# crypto_programmer.net
KiCad netlist of a schematic drawn in EAGLE
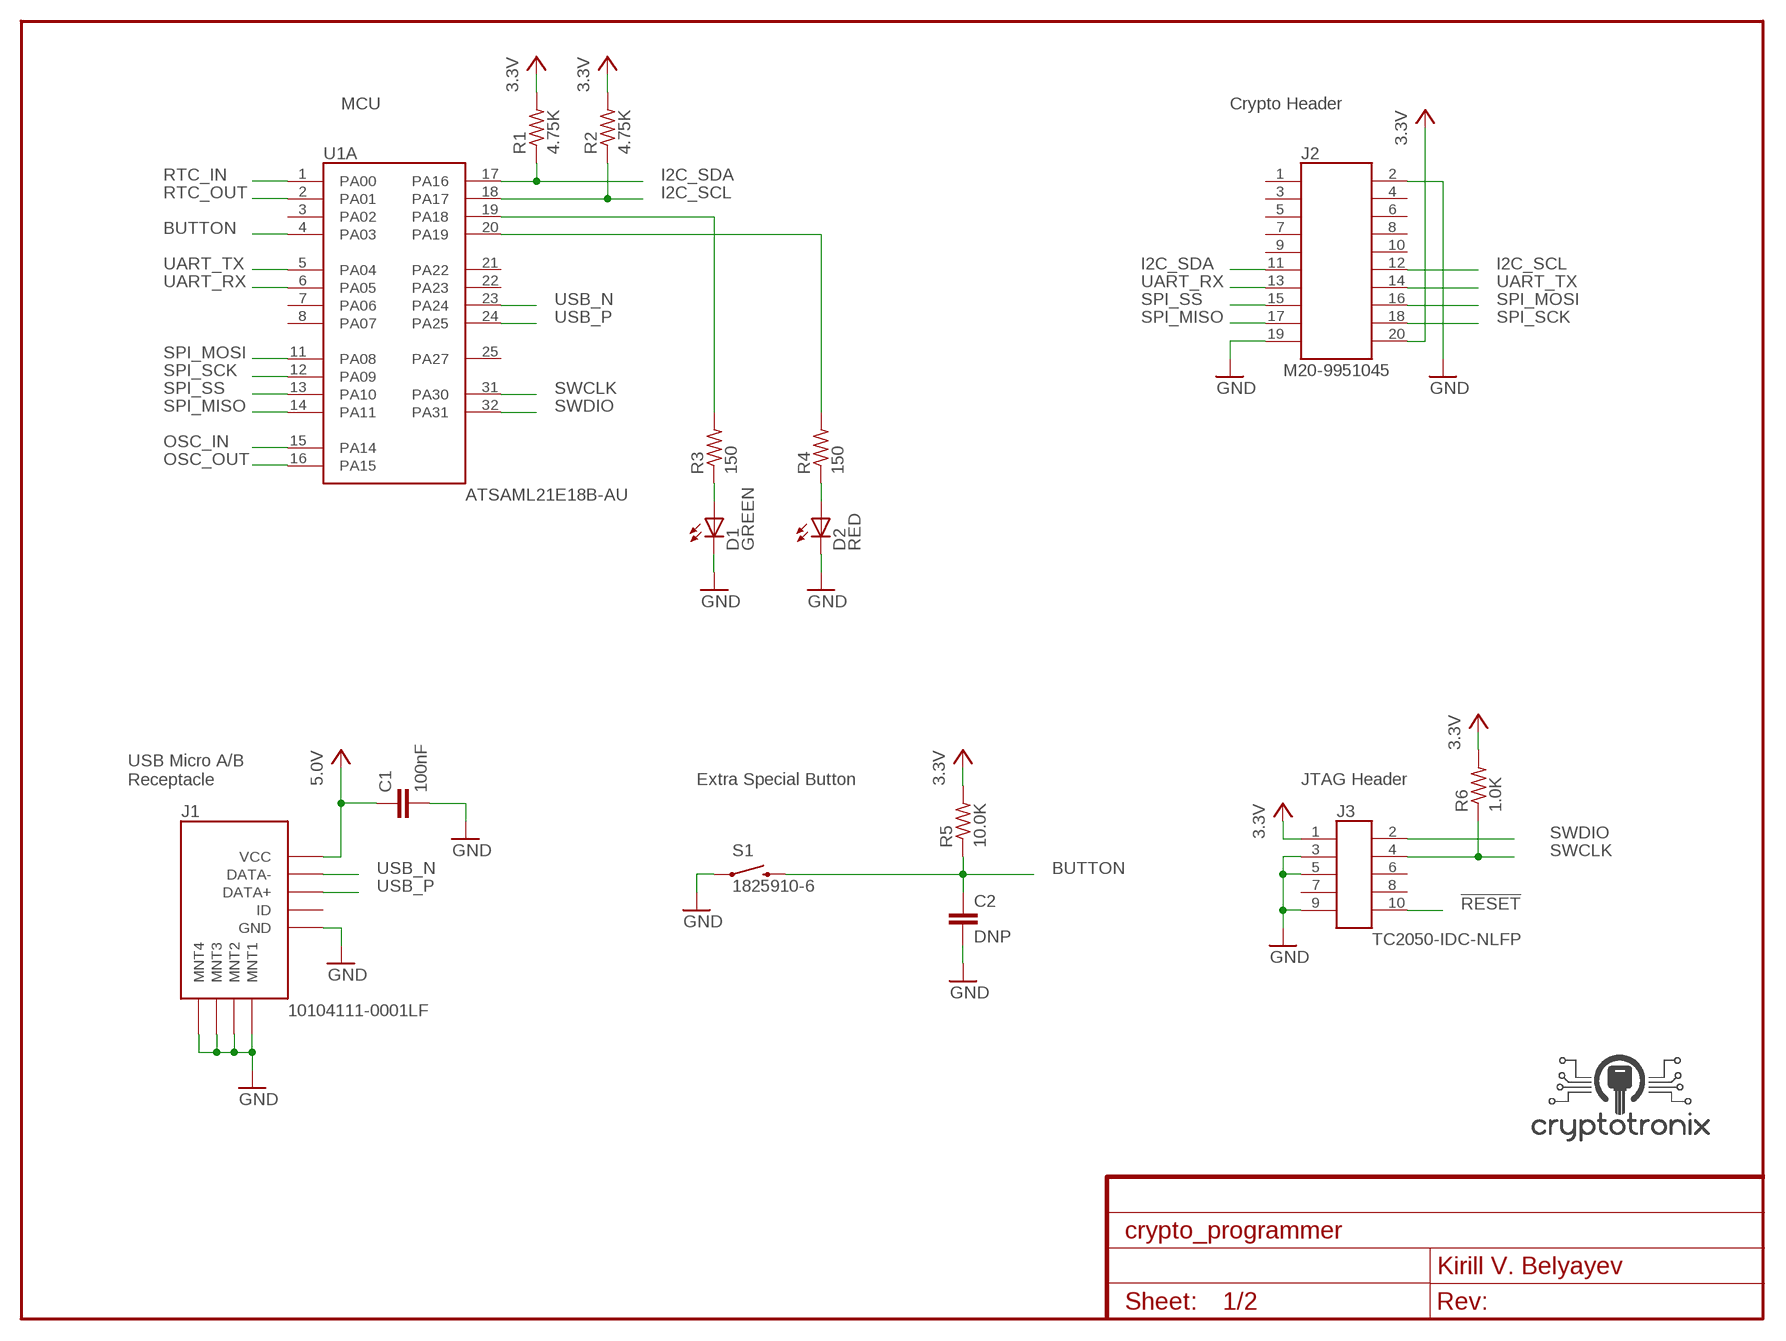
[diagram p0: schematic, sheet 1]
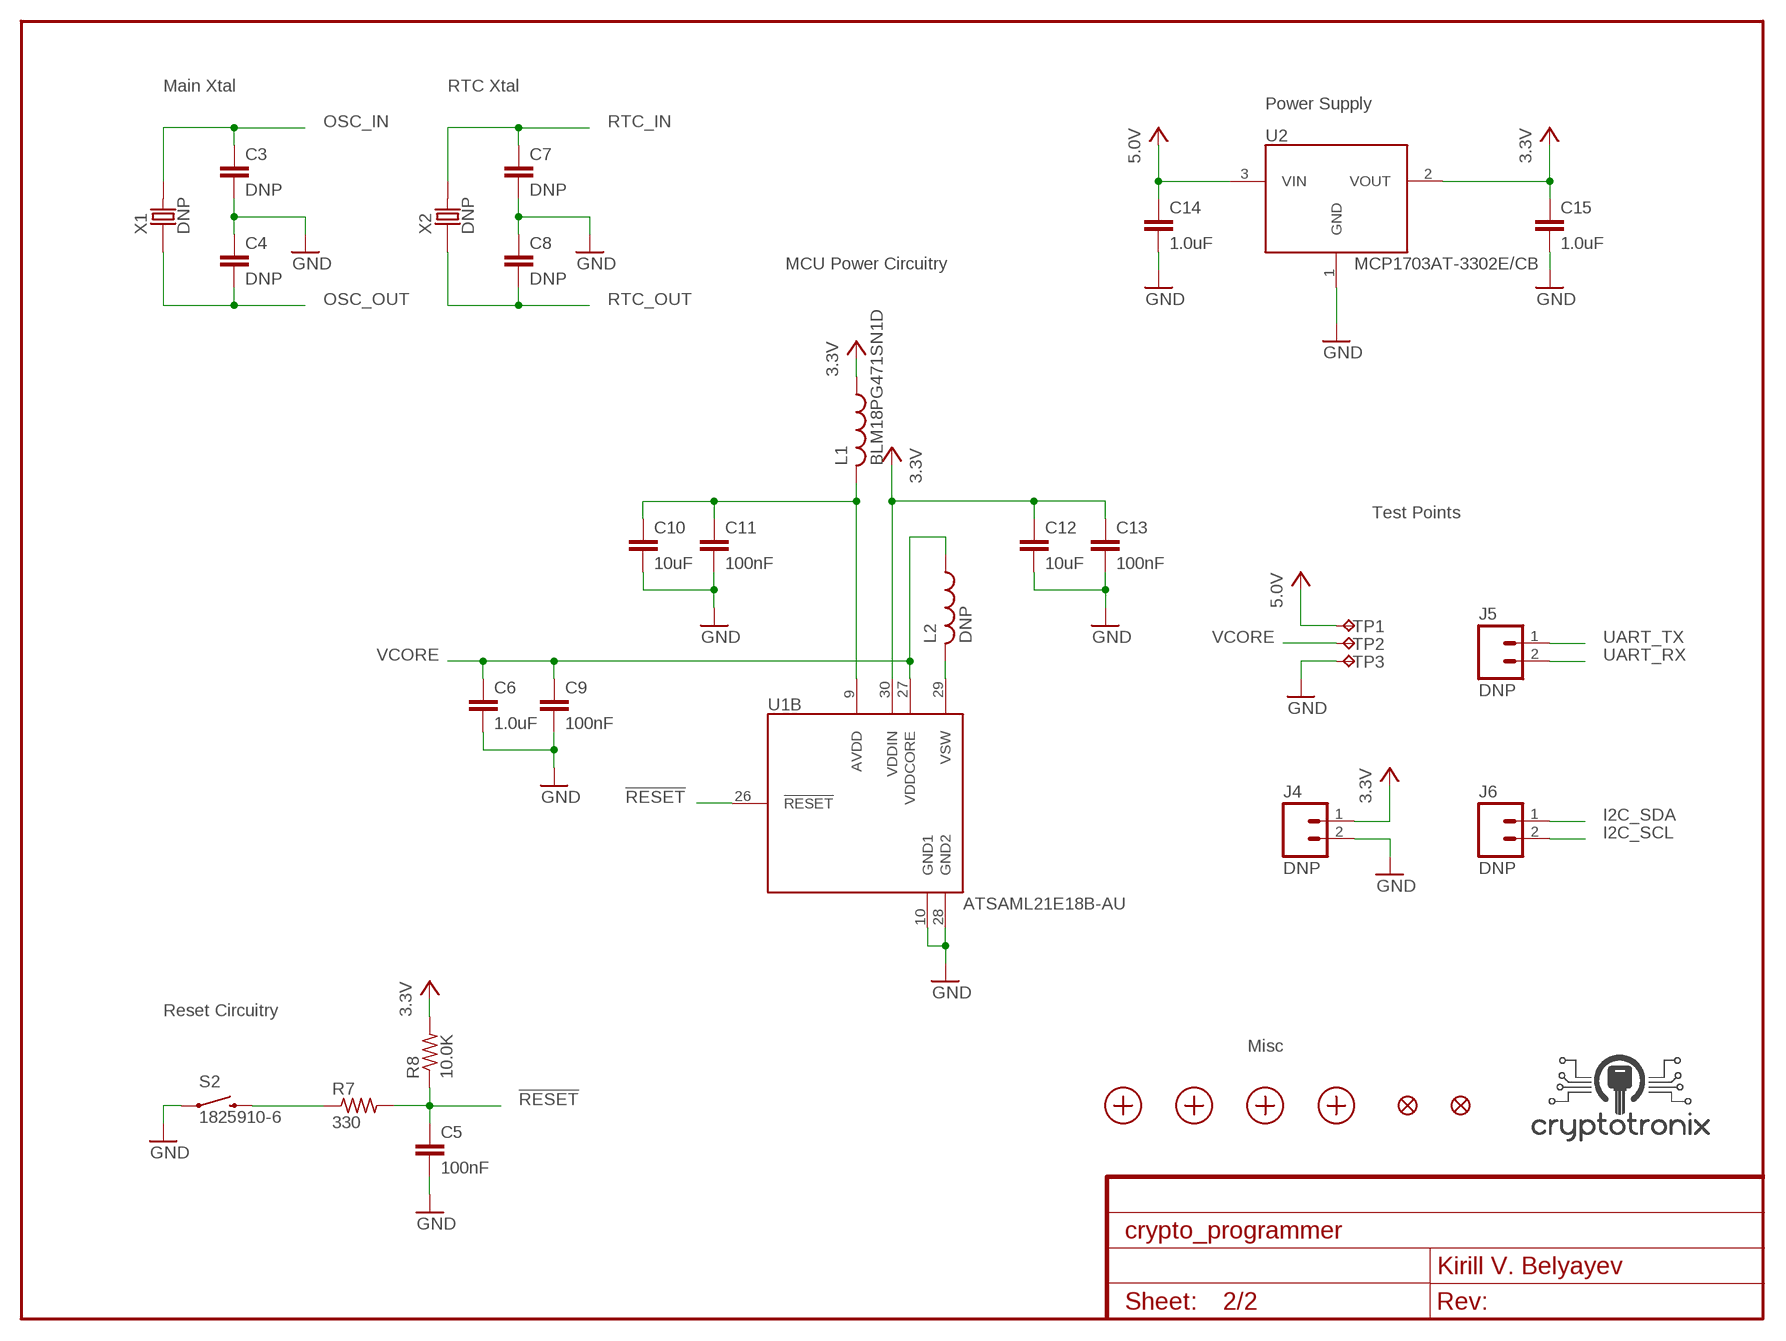
[diagram p1: schematic, sheet 2]

(export (version "E")
  (design (tool "Eeschema 10.0.6"))
  (components
    (comp (ref "C1")
      (value "100nF")
      (footprint "eagle-import:C0603")
      (libsource (lib "eagle-import") (part "C-EUC0603"))
    )
    (comp (ref "C2")
      (value "DNP")
      (footprint "eagle-import:C0603")
      (libsource (lib "eagle-import") (part "C-EUC0603"))
    )
    (comp (ref "D1")
      (value "GREEN")
      (footprint "eagle-import:0603")
      (fields (field (name "MAN-PART_NUM") "LTST-C190") (field (name "MANUFACTURER") "Lite-On Inc."))
      (libsource (lib "eagle-import") (part "LTST-C190GKT"))
    )
    (comp (ref "D2")
      (value "RED")
      (footprint "eagle-import:0603")
      (fields (field (name "MAN-PART_NUM") "LTST-C190") (field (name "MANUFACTURER") "Lite-On Inc."))
      (libsource (lib "eagle-import") (part "LTST-C190EKT"))
    )
    (comp (ref "J1")
      (value "10104111-0001LF")
      (footprint "eagle-import:10104111-0001LF")
      (fields (field (name "MANUFACTURER") "Amphenol"))
      (libsource (lib "eagle-import") (part "10104111-0001LF"))
    )
    (comp (ref "J2")
      (value "M20-9951045")
      (footprint "eagle-import:M20-9951045")
      (libsource (lib "eagle-import") (part "M20-9951045"))
    )
    (comp (ref "J3")
      (value "TC2050-IDC-NLFP")
      (footprint "eagle-import:TC2050-IDC-NLFP")
      (fields (field (name "MANUFACTURER") "Tag Connect"))
      (libsource (lib "eagle-import") (part "TC2050-IDC-NLFP"))
    )
    (comp (ref "LOGO1")
      (value "CRYPTOTRONIX_LOGO")
      (footprint "eagle-import:CRYPTOTRONIX_LOGO")
      (libsource (lib "eagle-import") (part "CRYPTOTRONIX_LOGO"))
    )
    (comp (ref "R1")
      (value "4.75K")
      (footprint "eagle-import:R0603")
      (libsource (lib "eagle-import") (part "R-US_R0603"))
    )
    (comp (ref "R2")
      (value "4.75K")
      (footprint "eagle-import:R0603")
      (libsource (lib "eagle-import") (part "R-US_R0603"))
    )
    (comp (ref "R3")
      (value "150")
      (footprint "eagle-import:R0603")
      (libsource (lib "eagle-import") (part "R-US_R0603"))
    )
    (comp (ref "R4")
      (value "150")
      (footprint "eagle-import:R0603")
      (libsource (lib "eagle-import") (part "R-US_R0603"))
    )
    (comp (ref "R5")
      (value "10.0K")
      (footprint "eagle-import:R0603")
      (libsource (lib "eagle-import") (part "R-US_R0603"))
    )
    (comp (ref "R6")
      (value "1.0K")
      (footprint "eagle-import:R0603")
      (libsource (lib "eagle-import") (part "R-US_R0603"))
    )
    (comp (ref "S1")
      (value "1825910-6")
      (footprint "eagle-import:SWITCH-TACT-TH")
      (fields
        (field (name "MANUFACTURER") "TE Connectivity")
        (field (name "MAN-PART_NUM") "1825910-6")
        (field (name "MANUFACTURER_1") "TE Connectivity")
      )
      (libsource (lib "eagle-import") (part "SWITCH-TACT-TH"))
    )
    (comp (ref "U1")
      (value "ATSAML21E18B-AU")
      (footprint "eagle-import:ATSAML21E18-AU")
      (fields (field (name "MAN-PART_NUM") "ATSAML21E18B-AUT") (field (name "MANUFACTURER") "Atmel"))
      (libsource (lib "eagle-import") (part "ATSAML21E18B-AU"))
    )
    (comp (ref "C3")
      (value "DNP")
      (footprint "eagle-import:C0603")
      (libsource (lib "eagle-import") (part "C-EUC0603"))
    )
    (comp (ref "C4")
      (value "DNP")
      (footprint "eagle-import:C0603")
      (libsource (lib "eagle-import") (part "C-EUC0603"))
    )
    (comp (ref "C5")
      (value "100nF")
      (footprint "eagle-import:C0603")
      (libsource (lib "eagle-import") (part "C-EUC0603"))
    )
    (comp (ref "C6")
      (value "1.0uF")
      (footprint "eagle-import:C0603")
      (libsource (lib "eagle-import") (part "C-EUC0603"))
    )
    (comp (ref "C7")
      (value "DNP")
      (footprint "eagle-import:C0603")
      (libsource (lib "eagle-import") (part "C-EUC0603"))
    )
    (comp (ref "C8")
      (value "DNP")
      (footprint "eagle-import:C0603")
      (libsource (lib "eagle-import") (part "C-EUC0603"))
    )
    (comp (ref "C9")
      (value "100nF")
      (footprint "eagle-import:C0603")
      (libsource (lib "eagle-import") (part "C-EUC0603"))
    )
    (comp (ref "C10")
      (value "10uF")
      (footprint "eagle-import:C0805")
      (libsource (lib "eagle-import") (part "C-EUC0805"))
    )
    (comp (ref "C11")
      (value "100nF")
      (footprint "eagle-import:C0603")
      (libsource (lib "eagle-import") (part "C-EUC0603"))
    )
    (comp (ref "C12")
      (value "10uF")
      (footprint "eagle-import:C0805")
      (libsource (lib "eagle-import") (part "C-EUC0805"))
    )
    (comp (ref "C13")
      (value "100nF")
      (footprint "eagle-import:C0603")
      (libsource (lib "eagle-import") (part "C-EUC0603"))
    )
    (comp (ref "C14")
      (value "1.0uF")
      (footprint "eagle-import:C0603")
      (libsource (lib "eagle-import") (part "C-EUC0603"))
    )
    (comp (ref "C15")
      (value "1.0uF")
      (footprint "eagle-import:C0603")
      (libsource (lib "eagle-import") (part "C-EUC0603"))
    )
    (comp (ref "FD1")
      (value "FIDUCIALUFIDUCIAL")
      (footprint "eagle-import:MICRO-FIDUCIAL")
      (libsource (lib "eagle-import") (part "FIDUCIALUFIDUCIAL"))
    )
    (comp (ref "FD2")
      (value "FIDUCIALUFIDUCIAL")
      (footprint "eagle-import:MICRO-FIDUCIAL")
      (libsource (lib "eagle-import") (part "FIDUCIALUFIDUCIAL"))
    )
    (comp (ref "J4")
      (value "DNP")
      (footprint "eagle-import:M20-9990246")
      (fields (field (name "MAN-PART_NUM") "M20-9990246") (field (name "MANUFACTURER") "Harwin Inc."))
      (libsource (lib "eagle-import") (part "M20-9990246"))
    )
    (comp (ref "J5")
      (value "DNP")
      (footprint "eagle-import:M20-9990246")
      (fields (field (name "MAN-PART_NUM") "M20-9990246") (field (name "MANUFACTURER") "Harwin Inc."))
      (libsource (lib "eagle-import") (part "M20-9990246"))
    )
    (comp (ref "J6")
      (value "DNP")
      (footprint "eagle-import:M20-9990246")
      (fields (field (name "MAN-PART_NUM") "M20-9990246") (field (name "MANUFACTURER") "Harwin Inc."))
      (libsource (lib "eagle-import") (part "M20-9990246"))
    )
    (comp (ref "L1")
      (value "BLM18PG471SN1D")
      (footprint "eagle-import:L0603")
      (libsource (lib "eagle-import") (part "L0603"))
    )
    (comp (ref "L2")
      (value "DNP")
      (footprint "eagle-import:L0603")
      (libsource (lib "eagle-import") (part "L0603"))
    )
    (comp (ref "LOGO2")
      (value "CRYPTOTRONIX_LOGO")
      (footprint "eagle-import:CRYPTOTRONIX_LOGO")
      (libsource (lib "eagle-import") (part "CRYPTOTRONIX_LOGO"))
    )
    (comp (ref "MNT1")
      (value "MOUNT-HOLE-NO-PLATE4-40")
      (footprint "eagle-import:MOUNT-HOLE-NO-PLATE-4-40")
      (libsource (lib "eagle-import") (part "MOUNT-HOLE-NO-PLATE4-40"))
    )
    (comp (ref "MNT2")
      (value "MOUNT-HOLE-NO-PLATE4-40")
      (footprint "eagle-import:MOUNT-HOLE-NO-PLATE-4-40")
      (libsource (lib "eagle-import") (part "MOUNT-HOLE-NO-PLATE4-40"))
    )
    (comp (ref "MNT3")
      (value "MOUNT-HOLE-NO-PLATE4-40")
      (footprint "eagle-import:MOUNT-HOLE-NO-PLATE-4-40")
      (libsource (lib "eagle-import") (part "MOUNT-HOLE-NO-PLATE4-40"))
    )
    (comp (ref "MNT4")
      (value "MOUNT-HOLE-NO-PLATE4-40")
      (footprint "eagle-import:MOUNT-HOLE-NO-PLATE-4-40")
      (libsource (lib "eagle-import") (part "MOUNT-HOLE-NO-PLATE4-40"))
    )
    (comp (ref "R7")
      (value "330")
      (footprint "eagle-import:R0603")
      (libsource (lib "eagle-import") (part "R-US_R0603"))
    )
    (comp (ref "R8")
      (value "10.0K")
      (footprint "eagle-import:R0603")
      (libsource (lib "eagle-import") (part "R-US_R0603"))
    )
    (comp (ref "S2")
      (value "1825910-6")
      (footprint "eagle-import:SWITCH-TACT-TH")
      (fields
        (field (name "MANUFACTURER") "TE Connectivity")
        (field (name "MAN-PART_NUM") "1825910-6")
        (field (name "MANUFACTURER_1") "TE Connectivity")
      )
      (libsource (lib "eagle-import") (part "SWITCH-TACT-TH"))
    )
    (comp (ref "TP1")
      (value "TEST-POINT40MIL")
      (footprint "eagle-import:TEST-POINT-40MILL")
      (libsource (lib "eagle-import") (part "TEST-POINT40MIL"))
    )
    (comp (ref "TP2")
      (value "TEST-POINT40MIL")
      (footprint "eagle-import:TEST-POINT-40MILL")
      (libsource (lib "eagle-import") (part "TEST-POINT40MIL"))
    )
    (comp (ref "TP3")
      (value "TEST-POINT40MIL")
      (footprint "eagle-import:TEST-POINT-40MILL")
      (libsource (lib "eagle-import") (part "TEST-POINT40MIL"))
    )
    (comp (ref "U2")
      (value "MCP1703AT-3302E/CB")
      (footprint "eagle-import:MCP1703AT-3302E_CB")
      (fields (field (name "MANUFACTURER") "Microchip Technology"))
      (libsource (lib "eagle-import") (part "MCP1703AT-3302E/CB"))
    )
    (comp (ref "X1")
      (value "DNP")
      (footprint "eagle-import:ABL-8.000MHZ-B2")
      (fields (field (name "MAN-PART_NUM") "ABL-8.000MHZ-B2") (field (name "MANUFACTURER") "Abracon"))
      (libsource (lib "eagle-import") (part "ABL-8.000MHZ-B2"))
    )
    (comp (ref "X2")
      (value "DNP")
      (footprint "eagle-import:ABS07AIG-32.768KHZ-9-T")
      (fields (field (name "MAN-PART_NUM") "ABS07AIG-32.768KHZ-9-T") (field (name "MANUFACTURER") "Abracon"))
      (libsource (lib "eagle-import") (part "ABS07AIG-32.768KHZ-9-T"))
    )
  )
  (nets
    (net (code "1") (name "0V") (class "Default")
      (node (ref "C1") (pin "2") (pinfunction "2_2") (pintype "passive"))
      (node (ref "C10") (pin "2") (pinfunction "2_2") (pintype "passive"))
      (node (ref "C11") (pin "2") (pinfunction "2_2") (pintype "passive"))
      (node (ref "C12") (pin "2") (pinfunction "2_2") (pintype "passive"))
      (node (ref "C13") (pin "2") (pinfunction "2_2") (pintype "passive"))
      (node (ref "C14") (pin "2") (pinfunction "2_2") (pintype "passive"))
      (node (ref "C15") (pin "2") (pinfunction "2_2") (pintype "passive"))
      (node (ref "C2") (pin "2") (pinfunction "2_2") (pintype "passive"))
      (node (ref "C3") (pin "2") (pinfunction "2_2") (pintype "passive"))
      (node (ref "C4") (pin "1") (pinfunction "1_1") (pintype "passive"))
      (node (ref "C5") (pin "2") (pinfunction "2_2") (pintype "passive"))
      (node (ref "C6") (pin "2") (pinfunction "2_2") (pintype "passive"))
      (node (ref "C7") (pin "2") (pinfunction "2_2") (pintype "passive"))
      (node (ref "C8") (pin "1") (pinfunction "1_1") (pintype "passive"))
      (node (ref "C9") (pin "2") (pinfunction "2_2") (pintype "passive"))
      (node (ref "D1") (pin "C") (pinfunction "C_C") (pintype "passive"))
      (node (ref "D2") (pin "C") (pinfunction "C_C") (pintype "passive"))
      (node (ref "J1") (pin "P$5") (pinfunction "GND_P$5") (pintype "bidirectional"))
      (node (ref "J1") (pin "P$6") (pinfunction "MNT1_P$6") (pintype "bidirectional"))
      (node (ref "J1") (pin "P$7") (pinfunction "MNT2_P$7") (pintype "bidirectional"))
      (node (ref "J1") (pin "P$8") (pinfunction "MNT3_P$8") (pintype "bidirectional"))
      (node (ref "J1") (pin "P$9") (pinfunction "MNT4_P$9") (pintype "bidirectional"))
      (node (ref "J2") (pin "19") (pinfunction "P$19_19") (pintype "bidirectional"))
      (node (ref "J2") (pin "2") (pinfunction "P$2_2") (pintype "bidirectional"))
      (node (ref "J3") (pin "3") (pinfunction "P$3_3") (pintype "bidirectional"))
      (node (ref "J3") (pin "5") (pinfunction "P$5_5") (pintype "bidirectional"))
      (node (ref "J3") (pin "9") (pinfunction "P$9_9") (pintype "bidirectional"))
      (node (ref "J4") (pin "2") (pinfunction "2_2") (pintype "passive"))
      (node (ref "S1") (pin "1") (pinfunction "1_1") (pintype "passive"))
      (node (ref "S2") (pin "1") (pinfunction "1_1") (pintype "passive"))
      (node (ref "TP3") (pin "1") (pinfunction "PP_1") (pintype "input"))
      (node (ref "U1") (pin "10") (pinfunction "GND1_10") (pintype "bidirectional"))
      (node (ref "U1") (pin "28") (pinfunction "GND2_28") (pintype "bidirectional"))
      (node (ref "U2") (pin "1") (pinfunction "GND_1") (pintype "bidirectional"))
    )
    (net (code "2") (name "3.3V") (class "Default")
      (node (ref "C12") (pin "1") (pinfunction "1_1") (pintype "passive"))
      (node (ref "C13") (pin "1") (pinfunction "1_1") (pintype "passive"))
      (node (ref "C15") (pin "1") (pinfunction "1_1") (pintype "passive"))
      (node (ref "J2") (pin "20") (pinfunction "P$20_20") (pintype "bidirectional"))
      (node (ref "J3") (pin "1") (pinfunction "P$1_1") (pintype "bidirectional"))
      (node (ref "J4") (pin "1") (pinfunction "1_1") (pintype "passive"))
      (node (ref "L1") (pin "1") (pinfunction "1_1") (pintype "passive"))
      (node (ref "R1") (pin "2") (pinfunction "2_2") (pintype "passive"))
      (node (ref "R2") (pin "2") (pinfunction "2_2") (pintype "passive"))
      (node (ref "R5") (pin "2") (pinfunction "2_2") (pintype "passive"))
      (node (ref "R6") (pin "2") (pinfunction "2_2") (pintype "passive"))
      (node (ref "R8") (pin "2") (pinfunction "2_2") (pintype "passive"))
      (node (ref "U1") (pin "30") (pinfunction "VDDIN_30") (pintype "bidirectional"))
      (node (ref "U2") (pin "2") (pinfunction "VOUT_2") (pintype "bidirectional"))
    )
    (net (code "3") (name "5.0V") (class "Default")
      (node (ref "C1") (pin "1") (pinfunction "1_1") (pintype "passive"))
      (node (ref "C14") (pin "1") (pinfunction "1_1") (pintype "passive"))
      (node (ref "J1") (pin "P$1") (pinfunction "VCC_P$1") (pintype "bidirectional"))
      (node (ref "TP1") (pin "1") (pinfunction "PP_1") (pintype "input"))
      (node (ref "U2") (pin "3") (pinfunction "VIN_3") (pintype "bidirectional"))
    )
    (net (code "4") (name "BUTTON") (class "Default")
      (node (ref "C2") (pin "1") (pinfunction "1_1") (pintype "passive"))
      (node (ref "R5") (pin "1") (pinfunction "1_1") (pintype "passive"))
      (node (ref "S1") (pin "3") (pinfunction "2_3") (pintype "passive"))
      (node (ref "U1") (pin "4") (pinfunction "PA03_4") (pintype "bidirectional"))
    )
    (net (code "5") (name "I2C_SCL") (class "Default")
      (node (ref "J2") (pin "12") (pinfunction "P$12_12") (pintype "bidirectional"))
      (node (ref "J6") (pin "2") (pinfunction "2_2") (pintype "passive"))
      (node (ref "R2") (pin "1") (pinfunction "1_1") (pintype "passive"))
      (node (ref "U1") (pin "18") (pinfunction "PA17_18") (pintype "bidirectional"))
    )
    (net (code "6") (name "I2C_SDA") (class "Default")
      (node (ref "J2") (pin "11") (pinfunction "P$11_11") (pintype "bidirectional"))
      (node (ref "J6") (pin "1") (pinfunction "1_1") (pintype "passive"))
      (node (ref "R1") (pin "1") (pinfunction "1_1") (pintype "passive"))
      (node (ref "U1") (pin "17") (pinfunction "PA16_17") (pintype "bidirectional"))
    )
    (net (code "7") (name "Net-(D1-PadA)") (class "Default")
      (node (ref "D1") (pin "A") (pinfunction "A_A") (pintype "passive"))
      (node (ref "R3") (pin "1") (pinfunction "1_1") (pintype "passive"))
    )
    (net (code "8") (name "Net-(D2-PadA)") (class "Default")
      (node (ref "D2") (pin "A") (pinfunction "A_A") (pintype "passive"))
      (node (ref "R4") (pin "1") (pinfunction "1_1") (pintype "passive"))
    )
    (net (code "9") (name "Net-(S2-2)") (class "Default")
      (node (ref "R7") (pin "1") (pinfunction "1_1") (pintype "passive"))
      (node (ref "S2") (pin "3") (pinfunction "2_3") (pintype "passive"))
    )
    (net (code "10") (name "Net-(U1A-PA18)") (class "Default")
      (node (ref "R3") (pin "2") (pinfunction "2_2") (pintype "passive"))
      (node (ref "U1") (pin "19") (pinfunction "PA18_19") (pintype "bidirectional"))
    )
    (net (code "11") (name "Net-(U1A-PA19)") (class "Default")
      (node (ref "R4") (pin "2") (pinfunction "2_2") (pintype "passive"))
      (node (ref "U1") (pin "20") (pinfunction "PA19_20") (pintype "bidirectional"))
    )
    (net (code "12") (name "Net-(U1B-AVDD)") (class "Default")
      (node (ref "C10") (pin "1") (pinfunction "1_1") (pintype "passive"))
      (node (ref "C11") (pin "1") (pinfunction "1_1") (pintype "passive"))
      (node (ref "L1") (pin "2") (pinfunction "2_2") (pintype "passive"))
      (node (ref "U1") (pin "9") (pinfunction "AVDD_9") (pintype "bidirectional"))
    )
    (net (code "13") (name "Net-(U1B-VSW)") (class "Default")
      (node (ref "L2") (pin "2") (pinfunction "2_2") (pintype "passive"))
      (node (ref "U1") (pin "29") (pinfunction "VSW_29") (pintype "bidirectional"))
    )
    (net (code "14") (name "OSC_IN") (class "Default")
      (node (ref "C3") (pin "1") (pinfunction "1_1") (pintype "passive"))
      (node (ref "U1") (pin "15") (pinfunction "PA14_15") (pintype "bidirectional"))
      (node (ref "X1") (pin "2") (pinfunction "2_2") (pintype "passive"))
    )
    (net (code "15") (name "OSC_OUT") (class "Default")
      (node (ref "C4") (pin "2") (pinfunction "2_2") (pintype "passive"))
      (node (ref "U1") (pin "16") (pinfunction "PA15_16") (pintype "bidirectional"))
      (node (ref "X1") (pin "1") (pinfunction "1_1") (pintype "passive"))
    )
    (net (code "16") (name "RTC_IN") (class "Default")
      (node (ref "C7") (pin "1") (pinfunction "1_1") (pintype "passive"))
      (node (ref "U1") (pin "1") (pinfunction "PA00_1") (pintype "bidirectional"))
      (node (ref "X2") (pin "2") (pinfunction "2_2") (pintype "passive"))
    )
    (net (code "17") (name "RTC_OUT") (class "Default")
      (node (ref "C8") (pin "2") (pinfunction "2_2") (pintype "passive"))
      (node (ref "U1") (pin "2") (pinfunction "PA01_2") (pintype "bidirectional"))
      (node (ref "X2") (pin "1") (pinfunction "1_1") (pintype "passive"))
    )
    (net (code "18") (name "SPI_MISO") (class "Default")
      (node (ref "J2") (pin "17") (pinfunction "P$17_17") (pintype "bidirectional"))
      (node (ref "U1") (pin "14") (pinfunction "PA11_14") (pintype "bidirectional"))
    )
    (net (code "19") (name "SPI_MOSI") (class "Default")
      (node (ref "J2") (pin "16") (pinfunction "P$16_16") (pintype "bidirectional"))
      (node (ref "U1") (pin "11") (pinfunction "PA08_11") (pintype "bidirectional"))
    )
    (net (code "20") (name "SPI_SCK") (class "Default")
      (node (ref "J2") (pin "18") (pinfunction "P$18_18") (pintype "bidirectional"))
      (node (ref "U1") (pin "12") (pinfunction "PA09_12") (pintype "bidirectional"))
    )
    (net (code "21") (name "SPI_SS") (class "Default")
      (node (ref "J2") (pin "15") (pinfunction "P$15_15") (pintype "bidirectional"))
      (node (ref "U1") (pin "13") (pinfunction "PA10_13") (pintype "bidirectional"))
    )
    (net (code "22") (name "SWCLK") (class "Default")
      (node (ref "J3") (pin "4") (pinfunction "P$4_4") (pintype "bidirectional"))
      (node (ref "R6") (pin "1") (pinfunction "1_1") (pintype "passive"))
      (node (ref "U1") (pin "31") (pinfunction "PA30_31") (pintype "bidirectional"))
    )
    (net (code "23") (name "SWDIO") (class "Default")
      (node (ref "J3") (pin "2") (pinfunction "P$2_2") (pintype "bidirectional"))
      (node (ref "U1") (pin "32") (pinfunction "PA31_32") (pintype "bidirectional"))
    )
    (net (code "24") (name "UART_RX") (class "Default")
      (node (ref "J2") (pin "13") (pinfunction "P$13_13") (pintype "bidirectional"))
      (node (ref "J5") (pin "2") (pinfunction "2_2") (pintype "passive"))
      (node (ref "U1") (pin "6") (pinfunction "PA05_6") (pintype "bidirectional"))
    )
    (net (code "25") (name "UART_TX") (class "Default")
      (node (ref "J2") (pin "14") (pinfunction "P$14_14") (pintype "bidirectional"))
      (node (ref "J5") (pin "1") (pinfunction "1_1") (pintype "passive"))
      (node (ref "U1") (pin "5") (pinfunction "PA04_5") (pintype "bidirectional"))
    )
    (net (code "26") (name "USB_N") (class "Default")
      (node (ref "J1") (pin "P$2") (pinfunction "DATA-_P$2") (pintype "bidirectional"))
      (node (ref "U1") (pin "23") (pinfunction "PA24_23") (pintype "bidirectional"))
    )
    (net (code "27") (name "USB_P") (class "Default")
      (node (ref "J1") (pin "P$3") (pinfunction "DATA+_P$3") (pintype "bidirectional"))
      (node (ref "U1") (pin "24") (pinfunction "PA25_24") (pintype "bidirectional"))
    )
    (net (code "28") (name "VCORE") (class "Default")
      (node (ref "C6") (pin "1") (pinfunction "1_1") (pintype "passive"))
      (node (ref "C9") (pin "1") (pinfunction "1_1") (pintype "passive"))
      (node (ref "L2") (pin "1") (pinfunction "1_1") (pintype "passive"))
      (node (ref "TP2") (pin "1") (pinfunction "PP_1") (pintype "input"))
      (node (ref "U1") (pin "27") (pinfunction "VDDCORE_27") (pintype "bidirectional"))
    )
    (net (code "29") (name "unconnected-(J1-ID-PadP$4)") (class "Default")
      (node (ref "J1") (pin "P$4") (pinfunction "ID_P$4") (pintype "bidirectional"))
    )
    (net (code "30") (name "unconnected-(J2-P$1-Pad1)") (class "Default")
      (node (ref "J2") (pin "1") (pinfunction "P$1_1") (pintype "bidirectional"))
    )
    (net (code "31") (name "unconnected-(J2-P$3-Pad3)") (class "Default")
      (node (ref "J2") (pin "3") (pinfunction "P$3_3") (pintype "bidirectional"))
    )
    (net (code "32") (name "unconnected-(J2-P$4-Pad4)") (class "Default")
      (node (ref "J2") (pin "4") (pinfunction "P$4_4") (pintype "bidirectional"))
    )
    (net (code "33") (name "unconnected-(J2-P$5-Pad5)") (class "Default")
      (node (ref "J2") (pin "5") (pinfunction "P$5_5") (pintype "bidirectional"))
    )
    (net (code "34") (name "unconnected-(J2-P$6-Pad6)") (class "Default")
      (node (ref "J2") (pin "6") (pinfunction "P$6_6") (pintype "bidirectional"))
    )
    (net (code "35") (name "unconnected-(J2-P$7-Pad7)") (class "Default")
      (node (ref "J2") (pin "7") (pinfunction "P$7_7") (pintype "bidirectional"))
    )
    (net (code "36") (name "unconnected-(J2-P$8-Pad8)") (class "Default")
      (node (ref "J2") (pin "8") (pinfunction "P$8_8") (pintype "bidirectional"))
    )
    (net (code "37") (name "unconnected-(J2-P$9-Pad9)") (class "Default")
      (node (ref "J2") (pin "9") (pinfunction "P$9_9") (pintype "bidirectional"))
    )
    (net (code "38") (name "unconnected-(J2-P$10-Pad10)") (class "Default")
      (node (ref "J2") (pin "10") (pinfunction "P$10_10") (pintype "bidirectional"))
    )
    (net (code "39") (name "unconnected-(J3-P$6-Pad6)") (class "Default")
      (node (ref "J3") (pin "6") (pinfunction "P$6_6") (pintype "bidirectional"))
    )
    (net (code "40") (name "unconnected-(J3-P$7-Pad7)") (class "Default")
      (node (ref "J3") (pin "7") (pinfunction "P$7_7") (pintype "bidirectional"))
    )
    (net (code "41") (name "unconnected-(J3-P$8-Pad8)") (class "Default")
      (node (ref "J3") (pin "8") (pinfunction "P$8_8") (pintype "bidirectional"))
    )
    (net (code "42") (name "unconnected-(U1A-PA02-Pad3)") (class "Default")
      (node (ref "U1") (pin "3") (pinfunction "PA02_3") (pintype "bidirectional"))
    )
    (net (code "43") (name "unconnected-(U1A-PA06-Pad7)") (class "Default")
      (node (ref "U1") (pin "7") (pinfunction "PA06_7") (pintype "bidirectional"))
    )
    (net (code "44") (name "unconnected-(U1A-PA07-Pad8)") (class "Default")
      (node (ref "U1") (pin "8") (pinfunction "PA07_8") (pintype "bidirectional"))
    )
    (net (code "45") (name "unconnected-(U1A-PA22-Pad21)") (class "Default")
      (node (ref "U1") (pin "21") (pinfunction "PA22_21") (pintype "bidirectional"))
    )
    (net (code "46") (name "unconnected-(U1A-PA23-Pad22)") (class "Default")
      (node (ref "U1") (pin "22") (pinfunction "PA23_22") (pintype "bidirectional"))
    )
    (net (code "47") (name "unconnected-(U1A-PA27-Pad25)") (class "Default")
      (node (ref "U1") (pin "25") (pinfunction "PA27_25") (pintype "bidirectional"))
    )
    (net (code "48") (name "~{RESET}") (class "Default")
      (node (ref "C5") (pin "1") (pinfunction "1_1") (pintype "passive"))
      (node (ref "J3") (pin "10") (pinfunction "P$10_10") (pintype "bidirectional"))
      (node (ref "R7") (pin "2") (pinfunction "2_2") (pintype "passive"))
      (node (ref "R8") (pin "1") (pinfunction "1_1") (pintype "passive"))
      (node (ref "U1") (pin "26") (pinfunction "~{RESET}_26") (pintype "bidirectional"))
    )
  )
)
